# MCU.net
KiCad netlist of a schematic drawn in Altium Designer
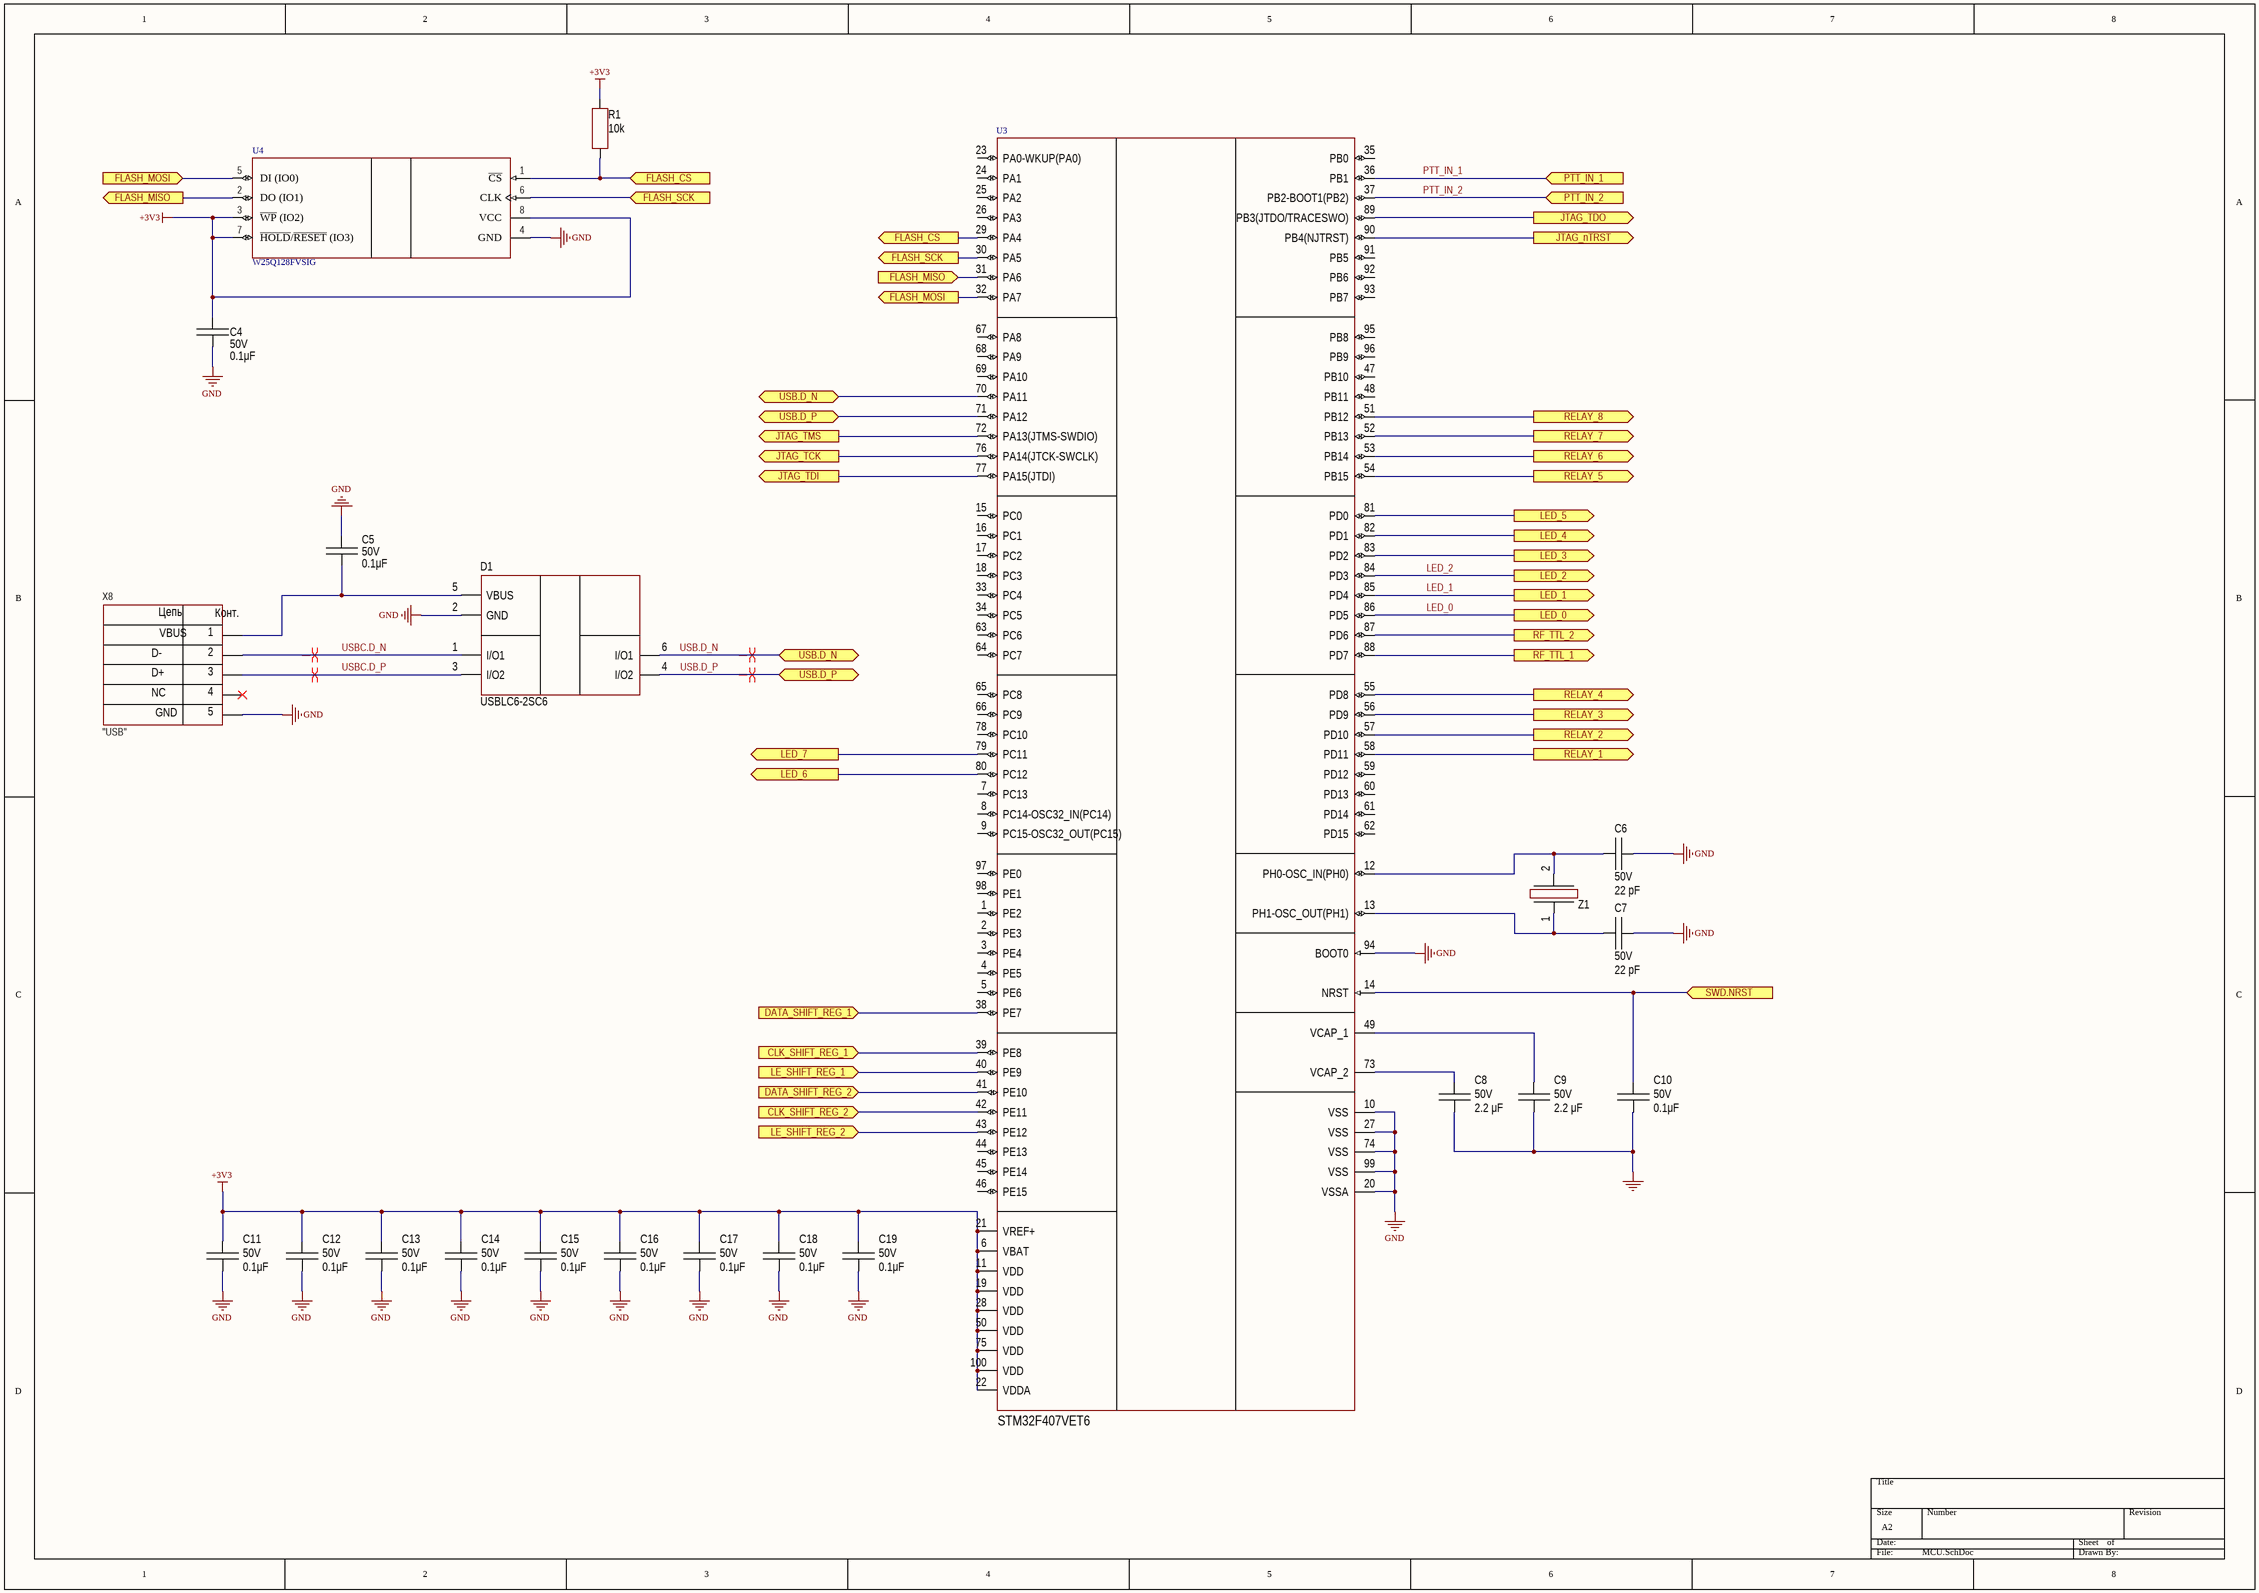
[diagram p0: MCU.SchDoc]

(export (version "E")
  (design (tool "Eeschema 10.0.6"))
  (components
    (comp (ref "C4")
      (value "0.1μF")
      (footprint "standard-case:CAP: 1206")
      (fields
        (field (name "MANUFACTURER") "Yageo")
        (field (name "PARTNUMBER") "CC1206KRX7R9BB104")
        (field (name "VALUEMANUFACTURERPARTNUMBER") "Ceramic capacitor, 0.1μF, X7R, ±10%, 50V, 1206, -55...+125°C")
        (field (name "VOLTAGE") "50V")
      )
      (libsource (lib "capacitor") (part "Ceramic_1206"))
    )
    (comp (ref "C5")
      (value "0.1μF")
      (footprint "standard-case:CAP: 1206")
      (fields
        (field (name "MANUFACTURER") "Yageo")
        (field (name "PARTNUMBER") "CC1206KRX7R9BB104")
        (field (name "VALUEMANUFACTURERPARTNUMBER") "Ceramic capacitor, 0.1μF, X7R, ±10%, 50V, 1206, -55...+125°C")
        (field (name "VOLTAGE") "50V")
      )
      (libsource (lib "capacitor") (part "Ceramic_1206"))
    )
    (comp (ref "C6")
      (value "22 pF")
      (footprint "standard-case:CAP: 1206")
      (fields
        (field (name "MANUFACTURER") "Yageo")
        (field (name "PARTNUMBER") "CC1206KRX7R9BB104")
        (field (name "VALUEMANUFACTURERPARTNUMBER") "Ceramic capacitor, 22 pF, X7R, ±10%, 50V, 1206, -55...+125°C")
        (field (name "VOLTAGE") "50V")
      )
      (libsource (lib "capacitor") (part "Ceramic_1206"))
    )
    (comp (ref "C7")
      (value "22 pF")
      (footprint "standard-case:CAP: 1206")
      (fields
        (field (name "MANUFACTURER") "Yageo")
        (field (name "PARTNUMBER") "CC1206KRX7R9BB104")
        (field (name "VALUEMANUFACTURERPARTNUMBER") "Ceramic capacitor, 22 pF, X7R, ±10%, 50V, 1206, -55...+125°C")
        (field (name "VOLTAGE") "50V")
      )
      (libsource (lib "capacitor") (part "Ceramic_1206"))
    )
    (comp (ref "C8")
      (value "2.2 μF")
      (footprint "standard-case:CAP: 1206")
      (fields
        (field (name "MANUFACTURER") "Yageo")
        (field (name "PARTNUMBER") "CC1206KRX7R9BB104")
        (field (name "VALUEMANUFACTURERPARTNUMBER") "Ceramic capacitor, 2.2 μF, X7R, ±10%, 50V, 1206, -55...+125°C")
        (field (name "VOLTAGE") "50V")
      )
      (libsource (lib "capacitor") (part "Ceramic_1206"))
    )
    (comp (ref "C9")
      (value "2.2 μF")
      (footprint "standard-case:CAP: 1206")
      (fields
        (field (name "MANUFACTURER") "Yageo")
        (field (name "PARTNUMBER") "CC1206KRX7R9BB104")
        (field (name "VALUEMANUFACTURERPARTNUMBER") "Ceramic capacitor, 2.2 μF, X7R, ±10%, 50V, 1206, -55...+125°C")
        (field (name "VOLTAGE") "50V")
      )
      (libsource (lib "capacitor") (part "Ceramic_1206"))
    )
    (comp (ref "C10")
      (value "0.1μF")
      (footprint "standard-case:CAP: 1206")
      (fields
        (field (name "MANUFACTURER") "Yageo")
        (field (name "PARTNUMBER") "CC1206KRX7R9BB104")
        (field (name "VALUEMANUFACTURERPARTNUMBER") "Ceramic capacitor, 0.1μF, X7R, ±10%, 50V, 1206, -55...+125°C")
        (field (name "VOLTAGE") "50V")
      )
      (libsource (lib "capacitor") (part "Ceramic_1206"))
    )
    (comp (ref "C11")
      (value "0.1μF")
      (footprint "standard-case:CAP: 1206")
      (fields
        (field (name "MANUFACTURER") "Yageo")
        (field (name "PARTNUMBER") "CC1206KRX7R9BB104")
        (field (name "VALUEMANUFACTURERPARTNUMBER") "Ceramic capacitor, 0.1μF, X7R, ±10%, 50V, 1206, -55...+125°C")
        (field (name "VOLTAGE") "50V")
      )
      (libsource (lib "capacitor") (part "Ceramic_1206"))
    )
    (comp (ref "C12")
      (value "0.1μF")
      (footprint "standard-case:CAP: 1206")
      (fields
        (field (name "MANUFACTURER") "Yageo")
        (field (name "PARTNUMBER") "CC1206KRX7R9BB104")
        (field (name "VALUEMANUFACTURERPARTNUMBER") "Ceramic capacitor, 0.1μF, X7R, ±10%, 50V, 1206, -55...+125°C")
        (field (name "VOLTAGE") "50V")
      )
      (libsource (lib "capacitor") (part "Ceramic_1206"))
    )
    (comp (ref "C13")
      (value "0.1μF")
      (footprint "standard-case:CAP: 1206")
      (fields
        (field (name "MANUFACTURER") "Yageo")
        (field (name "PARTNUMBER") "CC1206KRX7R9BB104")
        (field (name "VALUEMANUFACTURERPARTNUMBER") "Ceramic capacitor, 0.1μF, X7R, ±10%, 50V, 1206, -55...+125°C")
        (field (name "VOLTAGE") "50V")
      )
      (libsource (lib "capacitor") (part "Ceramic_1206"))
    )
    (comp (ref "C14")
      (value "0.1μF")
      (footprint "standard-case:CAP: 1206")
      (fields
        (field (name "MANUFACTURER") "Yageo")
        (field (name "PARTNUMBER") "CC1206KRX7R9BB104")
        (field (name "VALUEMANUFACTURERPARTNUMBER") "Ceramic capacitor, 0.1μF, X7R, ±10%, 50V, 1206, -55...+125°C")
        (field (name "VOLTAGE") "50V")
      )
      (libsource (lib "capacitor") (part "Ceramic_1206"))
    )
    (comp (ref "C15")
      (value "0.1μF")
      (footprint "standard-case:CAP: 1206")
      (fields
        (field (name "MANUFACTURER") "Yageo")
        (field (name "PARTNUMBER") "CC1206KRX7R9BB104")
        (field (name "VALUEMANUFACTURERPARTNUMBER") "Ceramic capacitor, 0.1μF, X7R, ±10%, 50V, 1206, -55...+125°C")
        (field (name "VOLTAGE") "50V")
      )
      (libsource (lib "capacitor") (part "Ceramic_1206"))
    )
    (comp (ref "C16")
      (value "0.1μF")
      (footprint "standard-case:CAP: 1206")
      (fields
        (field (name "MANUFACTURER") "Yageo")
        (field (name "PARTNUMBER") "CC1206KRX7R9BB104")
        (field (name "VALUEMANUFACTURERPARTNUMBER") "Ceramic capacitor, 0.1μF, X7R, ±10%, 50V, 1206, -55...+125°C")
        (field (name "VOLTAGE") "50V")
      )
      (libsource (lib "capacitor") (part "Ceramic_1206"))
    )
    (comp (ref "C17")
      (value "0.1μF")
      (footprint "standard-case:CAP: 1206")
      (fields
        (field (name "MANUFACTURER") "Yageo")
        (field (name "PARTNUMBER") "CC1206KRX7R9BB104")
        (field (name "VALUEMANUFACTURERPARTNUMBER") "Ceramic capacitor, 0.1μF, X7R, ±10%, 50V, 1206, -55...+125°C")
        (field (name "VOLTAGE") "50V")
      )
      (libsource (lib "capacitor") (part "Ceramic_1206"))
    )
    (comp (ref "C18")
      (value "0.1μF")
      (footprint "standard-case:CAP: 1206")
      (fields
        (field (name "MANUFACTURER") "Yageo")
        (field (name "PARTNUMBER") "CC1206KRX7R9BB104")
        (field (name "VALUEMANUFACTURERPARTNUMBER") "Ceramic capacitor, 0.1μF, X7R, ±10%, 50V, 1206, -55...+125°C")
        (field (name "VOLTAGE") "50V")
      )
      (libsource (lib "capacitor") (part "Ceramic_1206"))
    )
    (comp (ref "C19")
      (value "0.1μF")
      (footprint "standard-case:CAP: 1206")
      (fields
        (field (name "MANUFACTURER") "Yageo")
        (field (name "PARTNUMBER") "CC1206KRX7R9BB104")
        (field (name "VALUEMANUFACTURERPARTNUMBER") "Ceramic capacitor, 0.1μF, X7R, ±10%, 50V, 1206, -55...+125°C")
        (field (name "VOLTAGE") "50V")
      )
      (libsource (lib "capacitor") (part "Ceramic_1206"))
    )
    (comp (ref "D1")
      (value "~")
      (footprint "standard-case:SOT23-6")
      (fields
        (field (name "MANUFACTURER") "STMicroelectronics")
        (field (name "VALUEMANUFACTURERPARTNUMBER") "USB protection, , 5A peak, 17V, Power line, SOT-23-6, -40...+125°C")
        (field (name "PARTNUMBER") "USBLC6-2SC6")
      )
      (libsource (lib "diode") (part "USBLC6-2SC6"))
    )
    (comp (ref "R1")
      (value "10k")
      (footprint "RES: 1206")
      (fields
        (field (name "MANUFACTURER") "Yageo")
        (field (name "PARTNUMBER") "RC1206JR-07100RL")
        (field (name "VALUEMANUFACTURERPARTNUMBER") "Resistor film, 10k, , 1206, 0.25W, -55...+125°C")
      )
      (libsource (lib "R1206") (part "Resistor_1206"))
    )
    (comp (ref "U3")
      (value "STM32F407VET6")
      (footprint "STM-LQFP100_V")
      (fields (field (name "MANUFACTURER") "STMicroelectronics"))
      (libsource (lib "STM32F407VET6") (part "CMP-0243-00016-3"))
    )
    (comp (ref "U4")
      (value "W25Q128FVSIG")
      (footprint "8-SOIC")
      (fields (field (name "MANUFACTURER") "Winbond"))
      (libsource (lib "W25Q128FVSIG") (part "CMP-2000-05005-1"))
    )
    (comp (ref "X8")
      (value "~")
      (footprint "custom-case:CON: 0675031020")
      (fields
        (field (name "MANUFACTURER") "Molex")
        (field (name "VALUEMANUFACTURERPARTNUMBER") "USB mini B")
        (field (name "PARTNUMBER") "0675031020")
        (field (name "COMMENTTEXT") "\"USB\"")
      )
      (libsource (lib "connector") (part "Connector_USB_mini_B"))
    )
    (comp (ref "Z1")
      (value "~")
      (footprint "CTS-ATS-SM-XTAL-2")
      (fields
        (field (name "MANUFACTURER") "Epson")
        (field (name "PARTNUMBER") "FC-135 32.7680KA-A5")
        (field (name "VALUEMANUFACTURERPARTNUMBER") "Crystal, , 12.5pF, ±20ppm, case 3215, -40...+85°C")
      )
      (libsource (lib "HC-49SM") (part "Crystal_3215"))
    )
  )
  (nets
    (net (code "1") (name "+3V3") (class "Default")
      (node (ref "C11") (pin "2") (pinfunction "2_2") (pintype "passive"))
      (node (ref "C12") (pin "2") (pinfunction "2_2") (pintype "passive"))
      (node (ref "C13") (pin "2") (pinfunction "2_2") (pintype "passive"))
      (node (ref "C14") (pin "2") (pinfunction "2_2") (pintype "passive"))
      (node (ref "C15") (pin "2") (pinfunction "2_2") (pintype "passive"))
      (node (ref "C16") (pin "2") (pinfunction "2_2") (pintype "passive"))
      (node (ref "C17") (pin "2") (pinfunction "2_2") (pintype "passive"))
      (node (ref "C18") (pin "2") (pinfunction "2_2") (pintype "passive"))
      (node (ref "C19") (pin "2") (pinfunction "2_2") (pintype "passive"))
      (node (ref "C4") (pin "1") (pinfunction "1_1") (pintype "passive"))
      (node (ref "R1") (pin "1") (pinfunction "1_1") (pintype "passive"))
      (node (ref "U3") (pin "100") (pinfunction "VDD_100") (pintype "power_in"))
      (node (ref "U3") (pin "11") (pinfunction "VDD_11") (pintype "power_in"))
      (node (ref "U3") (pin "19") (pinfunction "VDD_19") (pintype "power_in"))
      (node (ref "U3") (pin "21") (pinfunction "VREF+_21") (pintype "power_in"))
      (node (ref "U3") (pin "22") (pinfunction "VDDA_22") (pintype "power_in"))
      (node (ref "U3") (pin "28") (pinfunction "VDD_28") (pintype "power_in"))
      (node (ref "U3") (pin "50") (pinfunction "VDD_50") (pintype "power_in"))
      (node (ref "U3") (pin "6") (pinfunction "VBAT_6") (pintype "power_in"))
      (node (ref "U3") (pin "75") (pinfunction "VDD_75") (pintype "power_in"))
      (node (ref "U4") (pin "3") (pinfunction "~{WP}_(IO2)_3") (pintype "bidirectional"))
      (node (ref "U4") (pin "7") (pinfunction "~{HOLD}/~{RESET}_(IO3)_7") (pintype "bidirectional"))
      (node (ref "U4") (pin "8") (pinfunction "VCC_8") (pintype "power_in"))
    )
    (net (code "2") (name "/CLK_SHIFT_REG_1") (class "Default")
      (node (ref "U3") (pin "39") (pinfunction "PE8_39") (pintype "bidirectional"))
    )
    (net (code "3") (name "/CLK_SHIFT_REG_2") (class "Default")
      (node (ref "U3") (pin "42") (pinfunction "PE11_42") (pintype "bidirectional"))
    )
    (net (code "4") (name "/DATA_SHIFT_REG_1") (class "Default")
      (node (ref "U3") (pin "38") (pinfunction "PE7_38") (pintype "bidirectional"))
    )
    (net (code "5") (name "/DATA_SHIFT_REG_2") (class "Default")
      (node (ref "U3") (pin "41") (pinfunction "PE10_41") (pintype "bidirectional"))
    )
    (net (code "6") (name "/FLASH_CS") (class "Default")
      (node (ref "R1") (pin "2") (pinfunction "2_2") (pintype "passive"))
      (node (ref "U3") (pin "29") (pinfunction "PA4_29") (pintype "bidirectional"))
      (node (ref "U4") (pin "1") (pinfunction "~{CS}_1") (pintype "input"))
    )
    (net (code "7") (name "/FLASH_MISO") (class "Default")
      (node (ref "U3") (pin "31") (pinfunction "PA6_31") (pintype "bidirectional"))
      (node (ref "U4") (pin "2") (pinfunction "DO_(IO1)_2") (pintype "bidirectional"))
    )
    (net (code "8") (name "/FLASH_MOSI") (class "Default")
      (node (ref "U3") (pin "32") (pinfunction "PA7_32") (pintype "bidirectional"))
      (node (ref "U4") (pin "5") (pinfunction "DI_(IO0)_5") (pintype "bidirectional"))
    )
    (net (code "9") (name "/FLASH_SCK") (class "Default")
      (node (ref "U3") (pin "30") (pinfunction "PA5_30") (pintype "bidirectional"))
      (node (ref "U4") (pin "6") (pinfunction "CLK_6") (pintype "input"))
    )
    (net (code "10") (name "/JTAG_TCK") (class "Default")
      (node (ref "U3") (pin "76") (pinfunction "PA14(JTCK-SWCLK)_76") (pintype "bidirectional"))
    )
    (net (code "11") (name "/JTAG_TDI") (class "Default")
      (node (ref "U3") (pin "77") (pinfunction "PA15(JTDI)_77") (pintype "bidirectional"))
    )
    (net (code "12") (name "/JTAG_TDO") (class "Default")
      (node (ref "U3") (pin "89") (pinfunction "PB3(JTDO/TRACESWO)_89") (pintype "bidirectional"))
    )
    (net (code "13") (name "/JTAG_TMS") (class "Default")
      (node (ref "U3") (pin "72") (pinfunction "PA13(JTMS-SWDIO)_72") (pintype "bidirectional"))
    )
    (net (code "14") (name "/JTAG_nTRST") (class "Default")
      (node (ref "U3") (pin "90") (pinfunction "PB4(NJTRST)_90") (pintype "bidirectional"))
    )
    (net (code "15") (name "/LED_0") (class "Default")
      (node (ref "U3") (pin "86") (pinfunction "PD5_86") (pintype "bidirectional"))
    )
    (net (code "16") (name "/LED_1") (class "Default")
      (node (ref "U3") (pin "85") (pinfunction "PD4_85") (pintype "bidirectional"))
    )
    (net (code "17") (name "/LED_2") (class "Default")
      (node (ref "U3") (pin "84") (pinfunction "PD3_84") (pintype "bidirectional"))
    )
    (net (code "18") (name "/LED_3") (class "Default")
      (node (ref "U3") (pin "83") (pinfunction "PD2_83") (pintype "bidirectional"))
    )
    (net (code "19") (name "/LED_4") (class "Default")
      (node (ref "U3") (pin "82") (pinfunction "PD1_82") (pintype "bidirectional"))
    )
    (net (code "20") (name "/LED_5") (class "Default")
      (node (ref "U3") (pin "81") (pinfunction "PD0_81") (pintype "bidirectional"))
    )
    (net (code "21") (name "/LED_6") (class "Default")
      (node (ref "U3") (pin "80") (pinfunction "PC12_80") (pintype "bidirectional"))
    )
    (net (code "22") (name "/LED_7") (class "Default")
      (node (ref "U3") (pin "79") (pinfunction "PC11_79") (pintype "bidirectional"))
    )
    (net (code "23") (name "/LE_SHIFT_REG_1") (class "Default")
      (node (ref "U3") (pin "40") (pinfunction "PE9_40") (pintype "bidirectional"))
    )
    (net (code "24") (name "/LE_SHIFT_REG_2") (class "Default")
      (node (ref "U3") (pin "43") (pinfunction "PE12_43") (pintype "bidirectional"))
    )
    (net (code "25") (name "/PTT_IN_1") (class "Default")
      (node (ref "U3") (pin "36") (pinfunction "PB1_36") (pintype "bidirectional"))
    )
    (net (code "26") (name "/PTT_IN_2") (class "Default")
      (node (ref "U3") (pin "37") (pinfunction "PB2-BOOT1(PB2)_37") (pintype "bidirectional"))
    )
    (net (code "27") (name "/RELAY_1") (class "Default")
      (node (ref "U3") (pin "58") (pinfunction "PD11_58") (pintype "bidirectional"))
    )
    (net (code "28") (name "/RELAY_2") (class "Default")
      (node (ref "U3") (pin "57") (pinfunction "PD10_57") (pintype "bidirectional"))
    )
    (net (code "29") (name "/RELAY_3") (class "Default")
      (node (ref "U3") (pin "56") (pinfunction "PD9_56") (pintype "bidirectional"))
    )
    (net (code "30") (name "/RELAY_4") (class "Default")
      (node (ref "U3") (pin "55") (pinfunction "PD8_55") (pintype "bidirectional"))
    )
    (net (code "31") (name "/RELAY_5") (class "Default")
      (node (ref "U3") (pin "54") (pinfunction "PB15_54") (pintype "bidirectional"))
    )
    (net (code "32") (name "/RELAY_6") (class "Default")
      (node (ref "U3") (pin "53") (pinfunction "PB14_53") (pintype "bidirectional"))
    )
    (net (code "33") (name "/RELAY_7") (class "Default")
      (node (ref "U3") (pin "52") (pinfunction "PB13_52") (pintype "bidirectional"))
    )
    (net (code "34") (name "/RELAY_8") (class "Default")
      (node (ref "U3") (pin "51") (pinfunction "PB12_51") (pintype "bidirectional"))
    )
    (net (code "35") (name "/RF_TTL_1") (class "Default")
      (node (ref "U3") (pin "88") (pinfunction "PD7_88") (pintype "bidirectional"))
    )
    (net (code "36") (name "/RF_TTL_2") (class "Default")
      (node (ref "U3") (pin "87") (pinfunction "PD6_87") (pintype "bidirectional"))
    )
    (net (code "37") (name "/SWD.NRST") (class "Default")
      (node (ref "C10") (pin "2") (pinfunction "2_2") (pintype "passive"))
      (node (ref "U3") (pin "14") (pinfunction "NRST_14") (pintype "input"))
    )
    (net (code "38") (name "/USB.D_N") (class "Default")
      (node (ref "D1") (pin "6") (pinfunction "I/O1_6") (pintype "passive"))
      (node (ref "U3") (pin "70") (pinfunction "PA11_70") (pintype "bidirectional"))
    )
    (net (code "39") (name "/USB.D_P") (class "Default")
      (node (ref "D1") (pin "4") (pinfunction "I/O2_4") (pintype "passive"))
      (node (ref "U3") (pin "71") (pinfunction "PA12_71") (pintype "bidirectional"))
    )
    (net (code "40") (name "/USBC.D_N") (class "Default")
      (node (ref "D1") (pin "1") (pinfunction "I/O1_1") (pintype "passive"))
      (node (ref "X8") (pin "2") (pinfunction "2_2") (pintype "passive"))
    )
    (net (code "41") (name "/USBC.D_P") (class "Default")
      (node (ref "D1") (pin "3") (pinfunction "I/O2_3") (pintype "passive"))
      (node (ref "X8") (pin "3") (pinfunction "3_3") (pintype "passive"))
    )
    (net (code "42") (name "GND") (class "Default")
      (node (ref "C10") (pin "1") (pinfunction "1_1") (pintype "passive"))
      (node (ref "C11") (pin "1") (pinfunction "1_1") (pintype "passive"))
      (node (ref "C12") (pin "1") (pinfunction "1_1") (pintype "passive"))
      (node (ref "C13") (pin "1") (pinfunction "1_1") (pintype "passive"))
      (node (ref "C14") (pin "1") (pinfunction "1_1") (pintype "passive"))
      (node (ref "C15") (pin "1") (pinfunction "1_1") (pintype "passive"))
      (node (ref "C16") (pin "1") (pinfunction "1_1") (pintype "passive"))
      (node (ref "C17") (pin "1") (pinfunction "1_1") (pintype "passive"))
      (node (ref "C18") (pin "1") (pinfunction "1_1") (pintype "passive"))
      (node (ref "C19") (pin "1") (pinfunction "1_1") (pintype "passive"))
      (node (ref "C4") (pin "2") (pinfunction "2_2") (pintype "passive"))
      (node (ref "C5") (pin "1") (pinfunction "1_1") (pintype "passive"))
      (node (ref "C6") (pin "1") (pinfunction "1_1") (pintype "passive"))
      (node (ref "C7") (pin "1") (pinfunction "1_1") (pintype "passive"))
      (node (ref "C8") (pin "1") (pinfunction "1_1") (pintype "passive"))
      (node (ref "C9") (pin "1") (pinfunction "1_1") (pintype "passive"))
      (node (ref "D1") (pin "2") (pinfunction "GND_2") (pintype "passive"))
      (node (ref "U3") (pin "10") (pinfunction "VSS_10") (pintype "power_in"))
      (node (ref "U3") (pin "20") (pinfunction "VSSA_20") (pintype "power_in"))
      (node (ref "U3") (pin "27") (pinfunction "VSS_27") (pintype "power_in"))
      (node (ref "U3") (pin "74") (pinfunction "VSS_74") (pintype "power_in"))
      (node (ref "U3") (pin "94") (pinfunction "BOOT0_94") (pintype "input"))
      (node (ref "U3") (pin "99") (pinfunction "VSS_99") (pintype "power_in"))
      (node (ref "U4") (pin "4") (pinfunction "GND_4") (pintype "power_in"))
      (node (ref "X8") (pin "5") (pinfunction "5_5") (pintype "passive"))
    )
    (net (code "43") (name "Net-(D1-VBUS)") (class "Default")
      (node (ref "C5") (pin "2") (pinfunction "2_2") (pintype "passive"))
      (node (ref "D1") (pin "5") (pinfunction "VBUS_5") (pintype "passive"))
      (node (ref "X8") (pin "1") (pintype "passive"))
    )
    (net (code "44") (name "Net-(U3-PH0-OSC_IN(PH0))") (class "Default")
      (node (ref "C6") (pin "2") (pinfunction "2_2") (pintype "passive"))
      (node (ref "U3") (pin "12") (pinfunction "PH0-OSC_IN(PH0)_12") (pintype "bidirectional"))
      (node (ref "Z1") (pin "2") (pinfunction "2_2") (pintype "passive"))
    )
    (net (code "45") (name "Net-(U3-PH1-OSC_OUT(PH1))") (class "Default")
      (node (ref "C7") (pin "2") (pinfunction "2_2") (pintype "passive"))
      (node (ref "U3") (pin "13") (pinfunction "PH1-OSC_OUT(PH1)_13") (pintype "bidirectional"))
      (node (ref "Z1") (pin "1") (pinfunction "1_1") (pintype "passive"))
    )
    (net (code "46") (name "Net-(U3-VCAP_1)") (class "Default")
      (node (ref "C9") (pin "2") (pinfunction "2_2") (pintype "passive"))
      (node (ref "U3") (pin "49") (pinfunction "VCAP_1_49") (pintype "power_in"))
    )
    (net (code "47") (name "Net-(U3-VCAP_2)") (class "Default")
      (node (ref "C8") (pin "2") (pinfunction "2_2") (pintype "passive"))
      (node (ref "U3") (pin "73") (pinfunction "VCAP_2_73") (pintype "power_in"))
    )
    (net (code "48") (name "unconnected-(U3-PA0-WKUP(PA0)-Pad23)") (class "Default")
      (node (ref "U3") (pin "23") (pinfunction "PA0-WKUP(PA0)_23") (pintype "bidirectional"))
    )
    (net (code "49") (name "unconnected-(U3-PA1-Pad24)") (class "Default")
      (node (ref "U3") (pin "24") (pinfunction "PA1_24") (pintype "bidirectional"))
    )
    (net (code "50") (name "unconnected-(U3-PA2-Pad25)") (class "Default")
      (node (ref "U3") (pin "25") (pinfunction "PA2_25") (pintype "bidirectional"))
    )
    (net (code "51") (name "unconnected-(U3-PA3-Pad26)") (class "Default")
      (node (ref "U3") (pin "26") (pinfunction "PA3_26") (pintype "bidirectional"))
    )
    (net (code "52") (name "unconnected-(U3-PA8-Pad67)") (class "Default")
      (node (ref "U3") (pin "67") (pinfunction "PA8_67") (pintype "bidirectional"))
    )
    (net (code "53") (name "unconnected-(U3-PA9-Pad68)") (class "Default")
      (node (ref "U3") (pin "68") (pinfunction "PA9_68") (pintype "bidirectional"))
    )
    (net (code "54") (name "unconnected-(U3-PA10-Pad69)") (class "Default")
      (node (ref "U3") (pin "69") (pinfunction "PA10_69") (pintype "bidirectional"))
    )
    (net (code "55") (name "unconnected-(U3-PB0-Pad35)") (class "Default")
      (node (ref "U3") (pin "35") (pinfunction "PB0_35") (pintype "bidirectional"))
    )
    (net (code "56") (name "unconnected-(U3-PB5-Pad91)") (class "Default")
      (node (ref "U3") (pin "91") (pinfunction "PB5_91") (pintype "bidirectional"))
    )
    (net (code "57") (name "unconnected-(U3-PB6-Pad92)") (class "Default")
      (node (ref "U3") (pin "92") (pinfunction "PB6_92") (pintype "bidirectional"))
    )
    (net (code "58") (name "unconnected-(U3-PB7-Pad93)") (class "Default")
      (node (ref "U3") (pin "93") (pinfunction "PB7_93") (pintype "bidirectional"))
    )
    (net (code "59") (name "unconnected-(U3-PB8-Pad95)") (class "Default")
      (node (ref "U3") (pin "95") (pinfunction "PB8_95") (pintype "bidirectional"))
    )
    (net (code "60") (name "unconnected-(U3-PB9-Pad96)") (class "Default")
      (node (ref "U3") (pin "96") (pinfunction "PB9_96") (pintype "bidirectional"))
    )
    (net (code "61") (name "unconnected-(U3-PB10-Pad47)") (class "Default")
      (node (ref "U3") (pin "47") (pinfunction "PB10_47") (pintype "bidirectional"))
    )
    (net (code "62") (name "unconnected-(U3-PB11-Pad48)") (class "Default")
      (node (ref "U3") (pin "48") (pinfunction "PB11_48") (pintype "bidirectional"))
    )
    (net (code "63") (name "unconnected-(U3-PC0-Pad15)") (class "Default")
      (node (ref "U3") (pin "15") (pinfunction "PC0_15") (pintype "bidirectional"))
    )
    (net (code "64") (name "unconnected-(U3-PC1-Pad16)") (class "Default")
      (node (ref "U3") (pin "16") (pinfunction "PC1_16") (pintype "bidirectional"))
    )
    (net (code "65") (name "unconnected-(U3-PC2-Pad17)") (class "Default")
      (node (ref "U3") (pin "17") (pinfunction "PC2_17") (pintype "bidirectional"))
    )
    (net (code "66") (name "unconnected-(U3-PC3-Pad18)") (class "Default")
      (node (ref "U3") (pin "18") (pinfunction "PC3_18") (pintype "bidirectional"))
    )
    (net (code "67") (name "unconnected-(U3-PC4-Pad33)") (class "Default")
      (node (ref "U3") (pin "33") (pinfunction "PC4_33") (pintype "bidirectional"))
    )
    (net (code "68") (name "unconnected-(U3-PC5-Pad34)") (class "Default")
      (node (ref "U3") (pin "34") (pinfunction "PC5_34") (pintype "bidirectional"))
    )
    (net (code "69") (name "unconnected-(U3-PC6-Pad63)") (class "Default")
      (node (ref "U3") (pin "63") (pinfunction "PC6_63") (pintype "bidirectional"))
    )
    (net (code "70") (name "unconnected-(U3-PC7-Pad64)") (class "Default")
      (node (ref "U3") (pin "64") (pinfunction "PC7_64") (pintype "bidirectional"))
    )
    (net (code "71") (name "unconnected-(U3-PC8-Pad65)") (class "Default")
      (node (ref "U3") (pin "65") (pinfunction "PC8_65") (pintype "bidirectional"))
    )
    (net (code "72") (name "unconnected-(U3-PC9-Pad66)") (class "Default")
      (node (ref "U3") (pin "66") (pinfunction "PC9_66") (pintype "bidirectional"))
    )
    (net (code "73") (name "unconnected-(U3-PC10-Pad78)") (class "Default")
      (node (ref "U3") (pin "78") (pinfunction "PC10_78") (pintype "bidirectional"))
    )
    (net (code "74") (name "unconnected-(U3-PC13-Pad7)") (class "Default")
      (node (ref "U3") (pin "7") (pinfunction "PC13_7") (pintype "bidirectional"))
    )
    (net (code "75") (name "unconnected-(U3-PC14-OSC32_IN(PC14)-Pad8)") (class "Default")
      (node (ref "U3") (pin "8") (pinfunction "PC14-OSC32_IN(PC14)_8") (pintype "bidirectional"))
    )
    (net (code "76") (name "unconnected-(U3-PC15-OSC32_OUT(PC15)-Pad9)") (class "Default")
      (node (ref "U3") (pin "9") (pinfunction "PC15-OSC32_OUT(PC15)_9") (pintype "bidirectional"))
    )
    (net (code "77") (name "unconnected-(U3-PD12-Pad59)") (class "Default")
      (node (ref "U3") (pin "59") (pinfunction "PD12_59") (pintype "bidirectional"))
    )
    (net (code "78") (name "unconnected-(U3-PD13-Pad60)") (class "Default")
      (node (ref "U3") (pin "60") (pinfunction "PD13_60") (pintype "bidirectional"))
    )
    (net (code "79") (name "unconnected-(U3-PD14-Pad61)") (class "Default")
      (node (ref "U3") (pin "61") (pinfunction "PD14_61") (pintype "bidirectional"))
    )
    (net (code "80") (name "unconnected-(U3-PD15-Pad62)") (class "Default")
      (node (ref "U3") (pin "62") (pinfunction "PD15_62") (pintype "bidirectional"))
    )
    (net (code "81") (name "unconnected-(U3-PE0-Pad97)") (class "Default")
      (node (ref "U3") (pin "97") (pinfunction "PE0_97") (pintype "bidirectional"))
    )
    (net (code "82") (name "unconnected-(U3-PE1-Pad98)") (class "Default")
      (node (ref "U3") (pin "98") (pinfunction "PE1_98") (pintype "bidirectional"))
    )
    (net (code "83") (name "unconnected-(U3-PE2-Pad1)") (class "Default")
      (node (ref "U3") (pin "1") (pinfunction "PE2_1") (pintype "bidirectional"))
    )
    (net (code "84") (name "unconnected-(U3-PE3-Pad2)") (class "Default")
      (node (ref "U3") (pin "2") (pinfunction "PE3_2") (pintype "bidirectional"))
    )
    (net (code "85") (name "unconnected-(U3-PE4-Pad3)") (class "Default")
      (node (ref "U3") (pin "3") (pinfunction "PE4_3") (pintype "bidirectional"))
    )
    (net (code "86") (name "unconnected-(U3-PE5-Pad4)") (class "Default")
      (node (ref "U3") (pin "4") (pinfunction "PE5_4") (pintype "bidirectional"))
    )
    (net (code "87") (name "unconnected-(U3-PE6-Pad5)") (class "Default")
      (node (ref "U3") (pin "5") (pinfunction "PE6_5") (pintype "bidirectional"))
    )
    (net (code "88") (name "unconnected-(U3-PE13-Pad44)") (class "Default")
      (node (ref "U3") (pin "44") (pinfunction "PE13_44") (pintype "bidirectional"))
    )
    (net (code "89") (name "unconnected-(U3-PE14-Pad45)") (class "Default")
      (node (ref "U3") (pin "45") (pinfunction "PE14_45") (pintype "bidirectional"))
    )
    (net (code "90") (name "unconnected-(U3-PE15-Pad46)") (class "Default")
      (node (ref "U3") (pin "46") (pinfunction "PE15_46") (pintype "bidirectional"))
    )
    (net (code "91") (name "unconnected-(X8-Pad4)") (class "Default")
      (node (ref "X8") (pin "4") (pinfunction "4_4") (pintype "passive+no_connect"))
    )
  )
)
